# USB-Isolator_v10.net
KiCad netlist of a schematic drawn in EAGLE
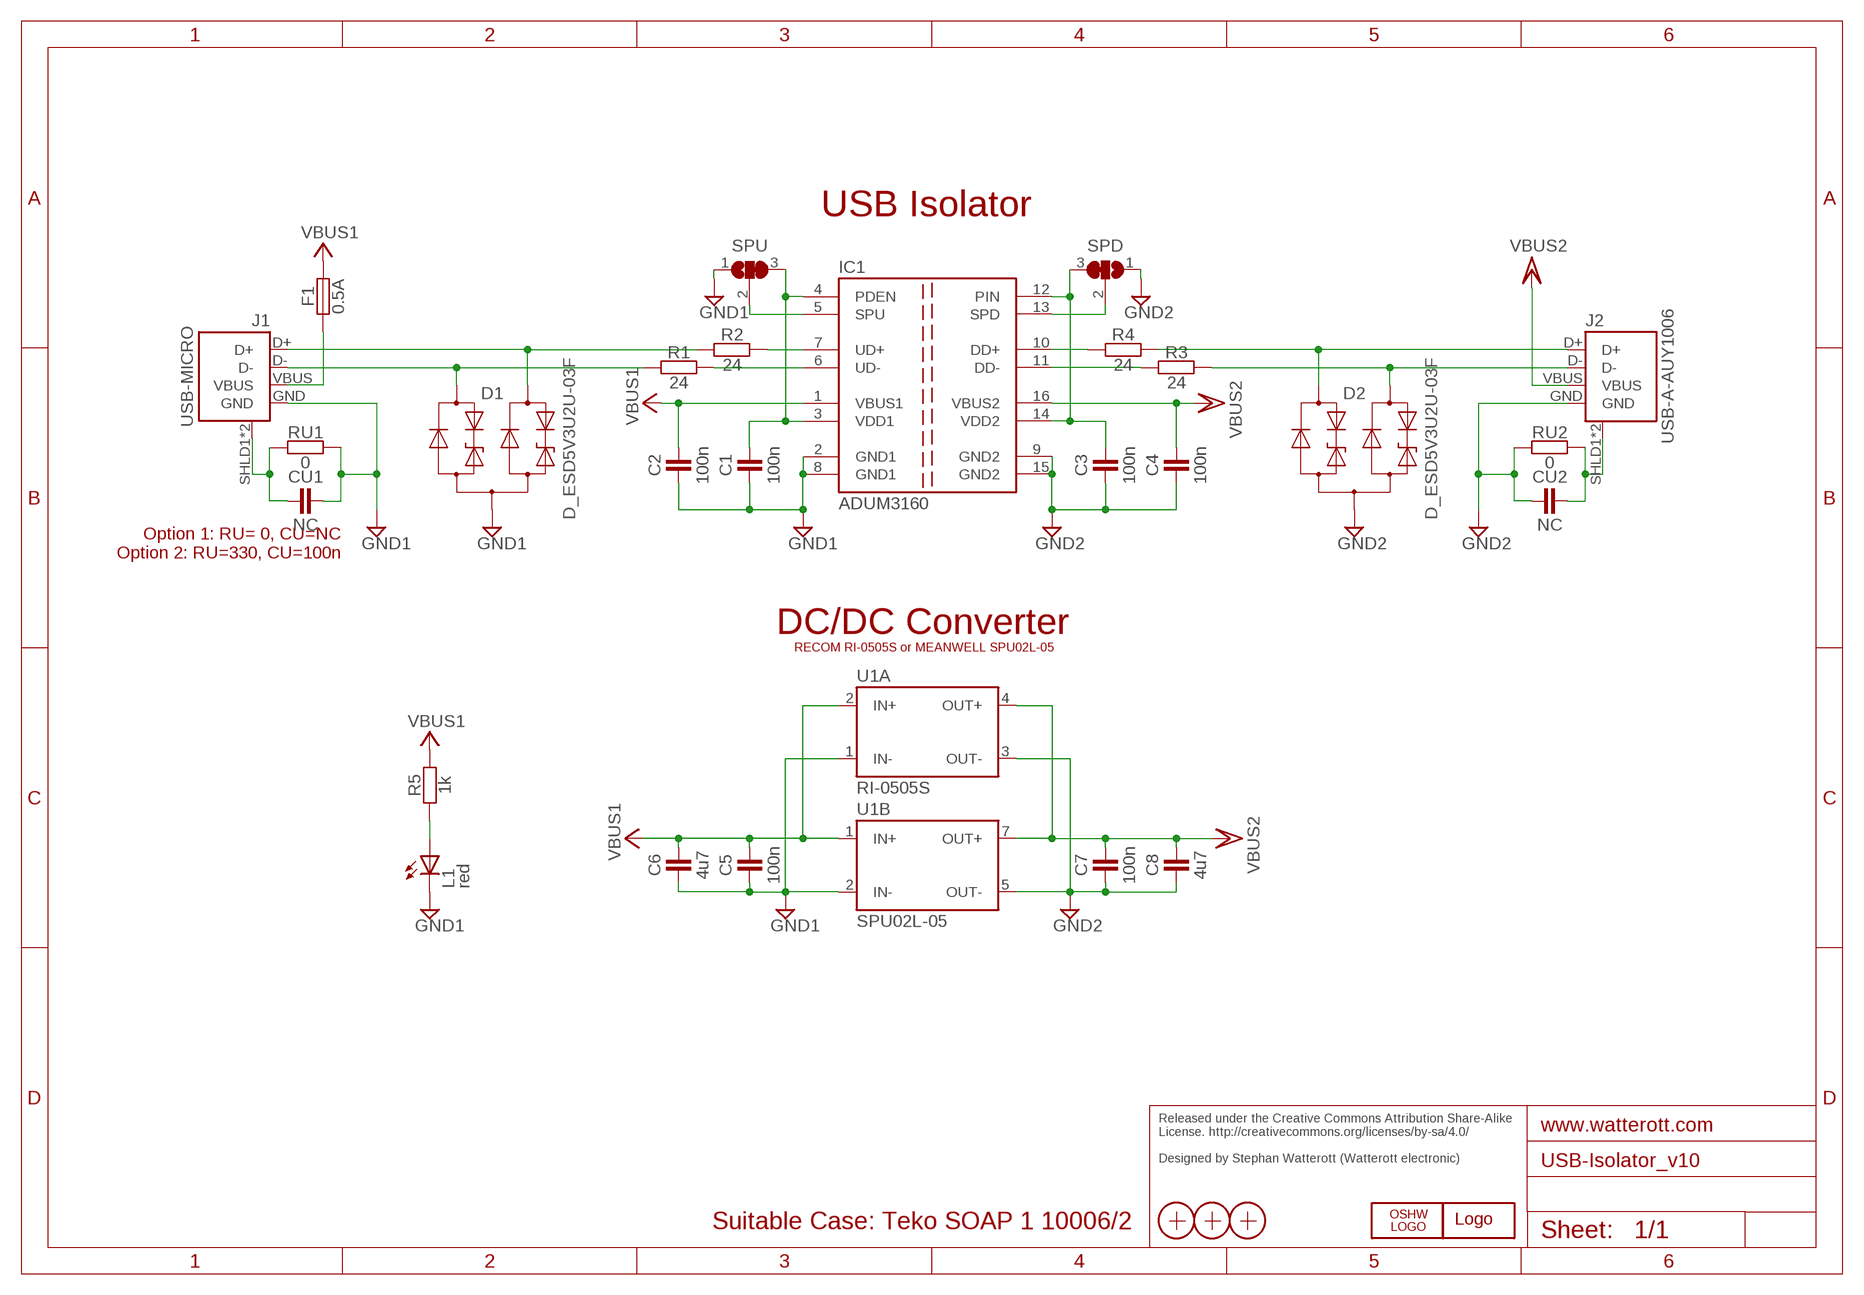
[diagram p0: schematic, sheet 1]

(export (version "E")
  (design (tool "Eeschema 10.0.6"))
  (components
    (comp (ref "C1")
      (value "100n")
      (footprint "eagle-import:R0603")
      (libsource (lib "eagle-import") (part "CAPACITOR-C0603"))
    )
    (comp (ref "C2")
      (value "100n")
      (footprint "eagle-import:R0603")
      (libsource (lib "eagle-import") (part "CAPACITOR-C0603"))
    )
    (comp (ref "C3")
      (value "100n")
      (footprint "eagle-import:R0603")
      (libsource (lib "eagle-import") (part "CAPACITOR-C0603"))
    )
    (comp (ref "C4")
      (value "100n")
      (footprint "eagle-import:R0603")
      (libsource (lib "eagle-import") (part "CAPACITOR-C0603"))
    )
    (comp (ref "C5")
      (value "100n")
      (footprint "eagle-import:R0603")
      (libsource (lib "eagle-import") (part "CAPACITOR-C0603"))
    )
    (comp (ref "C6")
      (value "4u7")
      (footprint "eagle-import:R1206")
      (libsource (lib "eagle-import") (part "CAPACITOR-C1206"))
    )
    (comp (ref "C7")
      (value "100n")
      (footprint "eagle-import:R0603")
      (libsource (lib "eagle-import") (part "CAPACITOR-C0603"))
    )
    (comp (ref "C8")
      (value "4u7")
      (footprint "eagle-import:R1206")
      (libsource (lib "eagle-import") (part "CAPACITOR-C1206"))
    )
    (comp (ref "CU1")
      (value "NC")
      (footprint "eagle-import:R0603")
      (libsource (lib "eagle-import") (part "CAPACITOR-C0603"))
    )
    (comp (ref "CU2")
      (value "NC")
      (footprint "eagle-import:R0603")
      (libsource (lib "eagle-import") (part "CAPACITOR-C0603"))
    )
    (comp (ref "D1")
      (value "D_ESD5V3U2U-03F")
      (footprint "eagle-import:TSFP3")
      (libsource (lib "eagle-import") (part "D_ESD5V3U2U-03F"))
    )
    (comp (ref "D2")
      (value "D_ESD5V3U2U-03F")
      (footprint "eagle-import:TSFP3")
      (libsource (lib "eagle-import") (part "D_ESD5V3U2U-03F"))
    )
    (comp (ref "F1")
      (value "0.5A")
      (footprint "eagle-import:R0805")
      (libsource (lib "eagle-import") (part "FUSE-0805"))
    )
    (comp (ref "IC1")
      (value "ADUM3160")
      (footprint "eagle-import:SO16W")
      (libsource (lib "eagle-import") (part "ADUM3160"))
    )
    (comp (ref "J1")
      (value "USB-MICRO")
      (footprint "eagle-import:USB-MICRO-10103594")
      (libsource (lib "eagle-import") (part "USB-MICRO"))
    )
    (comp (ref "J2")
      (value "USB-A-AUY1006")
      (footprint "eagle-import:USB-AU-Y1006-R")
      (fields (field (name "MANUFACTURER") "AU-Y1006-R"))
      (libsource (lib "eagle-import") (part "USB-A-AUY1006"))
    )
    (comp (ref "L1")
      (value "red")
      (footprint "eagle-import:LED_0603")
      (libsource (lib "eagle-import") (part "LED-0603"))
    )
    (comp (ref "LOGO2")
      (value "OSHW_LOGOX0070")
      (footprint "eagle-import:OSHW_6X70")
      (libsource (lib "eagle-import") (part "OSHW_LOGOX0070"))
    )
    (comp (ref "LOGO3")
      (value "LOGO-S_PLACE_M")
      (footprint "eagle-import:SPARK_TPLACE_M")
      (libsource (lib "eagle-import") (part "LOGO-S_PLACE_M"))
    )
    (comp (ref "R1")
      (value "24")
      (footprint "eagle-import:R0603")
      (libsource (lib "eagle-import") (part "RESISTOR-R0603"))
    )
    (comp (ref "R2")
      (value "24")
      (footprint "eagle-import:R0603")
      (libsource (lib "eagle-import") (part "RESISTOR-R0603"))
    )
    (comp (ref "R3")
      (value "24")
      (footprint "eagle-import:R0603")
      (libsource (lib "eagle-import") (part "RESISTOR-R0603"))
    )
    (comp (ref "R4")
      (value "24")
      (footprint "eagle-import:R0603")
      (libsource (lib "eagle-import") (part "RESISTOR-R0603"))
    )
    (comp (ref "R5")
      (value "1k")
      (footprint "eagle-import:R0603")
      (libsource (lib "eagle-import") (part "RESISTOR-R0603"))
    )
    (comp (ref "RU1")
      (value "0")
      (footprint "eagle-import:R0603")
      (libsource (lib "eagle-import") (part "RESISTOR-R0603"))
    )
    (comp (ref "RU2")
      (value "0")
      (footprint "eagle-import:R0603")
      (libsource (lib "eagle-import") (part "RESISTOR-R0603"))
    )
    (comp (ref "SPD")
      (value "JUMPER3")
      (footprint "eagle-import:JUMPER3")
      (libsource (lib "eagle-import") (part "JUMPER3"))
    )
    (comp (ref "SPU")
      (value "JUMPER3")
      (footprint "eagle-import:JUMPER3")
      (libsource (lib "eagle-import") (part "JUMPER3"))
    )
    (comp (ref "U1A")
      (value "RI-0505S")
      (footprint "eagle-import:RECOM_SIP4_RI")
      (libsource (lib "eagle-import") (part "DC/DC-RI"))
    )
    (comp (ref "U1B")
      (value "SPU02L-05")
      (footprint "eagle-import:MEANWELL_SIP7_SPU02")
      (libsource (lib "eagle-import") (part "DC/DC-SPU02"))
    )
    (comp (ref "X1")
      (value "PASSER-07")
      (footprint "eagle-import:PASSER_07MM")
      (libsource (lib "eagle-import") (part "PASSER-07"))
    )
    (comp (ref "X2")
      (value "PASSER-07")
      (footprint "eagle-import:PASSER_07MM")
      (libsource (lib "eagle-import") (part "PASSER-07"))
    )
    (comp (ref "X3")
      (value "PASSER-07")
      (footprint "eagle-import:PASSER_07MM")
      (libsource (lib "eagle-import") (part "PASSER-07"))
    )
  )
  (nets
    (net (code "1") (name "GND1") (class "Default")
      (node (ref "C1") (pin "1") (pinfunction "1_1") (pintype "passive"))
      (node (ref "C2") (pin "1") (pinfunction "1_1") (pintype "passive"))
      (node (ref "C5") (pin "1") (pinfunction "1_1") (pintype "passive"))
      (node (ref "C6") (pin "1") (pinfunction "1_1") (pintype "passive"))
      (node (ref "CU1") (pin "2") (pinfunction "2_2") (pintype "passive"))
      (node (ref "D1") (pin "3") (pinfunction "A_3") (pintype "passive"))
      (node (ref "IC1") (pin "2") (pinfunction "GND1_2") (pintype "power_in"))
      (node (ref "IC1") (pin "8") (pinfunction "GND1_8") (pintype "power_in"))
      (node (ref "J1") (pin "GND") (pinfunction "GND_GND") (pintype "power_in"))
      (node (ref "L1") (pin "C") (pinfunction "C_C") (pintype "passive"))
      (node (ref "RU1") (pin "2") (pinfunction "2_2") (pintype "passive"))
      (node (ref "SPU") (pin "1") (pinfunction "1_1") (pintype "passive"))
      (node (ref "U1A") (pin "1") (pinfunction "IN-_1") (pintype "power_in"))
      (node (ref "U1B") (pin "2") (pinfunction "IN-_2") (pintype "power_in"))
    )
    (net (code "2") (name "GND2") (class "Default")
      (node (ref "C3") (pin "1") (pinfunction "1_1") (pintype "passive"))
      (node (ref "C4") (pin "1") (pinfunction "1_1") (pintype "passive"))
      (node (ref "C7") (pin "1") (pinfunction "1_1") (pintype "passive"))
      (node (ref "C8") (pin "1") (pinfunction "1_1") (pintype "passive"))
      (node (ref "CU2") (pin "1") (pinfunction "1_1") (pintype "passive"))
      (node (ref "D2") (pin "3") (pinfunction "A_3") (pintype "passive"))
      (node (ref "IC1") (pin "15") (pinfunction "GND2_15") (pintype "power_in"))
      (node (ref "IC1") (pin "9") (pinfunction "GND2_9") (pintype "power_in"))
      (node (ref "J2") (pin "GND") (pinfunction "GND_GND") (pintype "power_in"))
      (node (ref "RU2") (pin "1") (pinfunction "1_1") (pintype "passive"))
      (node (ref "SPD") (pin "1") (pinfunction "1_1") (pintype "passive"))
      (node (ref "U1A") (pin "3") (pinfunction "OUT-_3") (pintype "power_in"))
      (node (ref "U1B") (pin "5") (pinfunction "OUT-_5") (pintype "power_in"))
    )
    (net (code "3") (name "Net-(CU1-Pad1)") (class "Default")
      (node (ref "CU1") (pin "1") (pinfunction "1_1") (pintype "passive"))
      (node (ref "J1") (pin "SHLD1") (pinfunction "SHIELD_SHLD1") (pintype "passive"))
      (node (ref "J1") (pin "SHLD2") (pinfunction "SHIELD_SHLD2") (pintype "passive"))
      (node (ref "RU1") (pin "1") (pinfunction "1_1") (pintype "passive"))
    )
    (net (code "4") (name "Net-(CU2-Pad2)") (class "Default")
      (node (ref "CU2") (pin "2") (pinfunction "2_2") (pintype "passive"))
      (node (ref "J2") (pin "SHLD1") (pinfunction "SHIELD_SHLD1") (pintype "passive"))
      (node (ref "J2") (pin "SHLD2") (pinfunction "SHIELD_SHLD2") (pintype "passive"))
      (node (ref "RU2") (pin "2") (pinfunction "2_2") (pintype "passive"))
    )
    (net (code "5") (name "Net-(D1-C1)") (class "Default")
      (node (ref "D1") (pin "1") (pinfunction "C1_1") (pintype "passive"))
      (node (ref "J1") (pin "D-") (pinfunction "D-_D-") (pintype "bidirectional"))
      (node (ref "R1") (pin "1") (pinfunction "1_1") (pintype "passive"))
    )
    (net (code "6") (name "Net-(D1-C2)") (class "Default")
      (node (ref "D1") (pin "2") (pinfunction "C2_2") (pintype "passive"))
      (node (ref "J1") (pin "D+") (pinfunction "D+_D+") (pintype "bidirectional"))
      (node (ref "R2") (pin "1") (pinfunction "1_1") (pintype "passive"))
    )
    (net (code "7") (name "Net-(D2-C1)") (class "Default")
      (node (ref "D2") (pin "1") (pinfunction "C1_1") (pintype "passive"))
      (node (ref "J2") (pin "D+") (pinfunction "D+_D+") (pintype "bidirectional"))
      (node (ref "R4") (pin "2") (pinfunction "2_2") (pintype "passive"))
    )
    (net (code "8") (name "Net-(D2-C2)") (class "Default")
      (node (ref "D2") (pin "2") (pinfunction "C2_2") (pintype "passive"))
      (node (ref "J2") (pin "D-") (pinfunction "D-_D-") (pintype "bidirectional"))
      (node (ref "R3") (pin "2") (pinfunction "2_2") (pintype "passive"))
    )
    (net (code "9") (name "Net-(F1-Pad1)") (class "Default")
      (node (ref "F1") (pin "1") (pinfunction "1_1") (pintype "passive"))
      (node (ref "J1") (pin "VBUS") (pinfunction "VBUS_VBUS") (pintype "power_in"))
    )
    (net (code "10") (name "Net-(IC1-DD+)") (class "Default")
      (node (ref "IC1") (pin "10") (pinfunction "DD+_10") (pintype "bidirectional"))
      (node (ref "R4") (pin "1") (pinfunction "1_1") (pintype "passive"))
    )
    (net (code "11") (name "Net-(IC1-DD-)") (class "Default")
      (node (ref "IC1") (pin "11") (pinfunction "DD-_11") (pintype "bidirectional"))
      (node (ref "R3") (pin "1") (pinfunction "1_1") (pintype "passive"))
    )
    (net (code "12") (name "Net-(IC1-PDEN)") (class "Default")
      (node (ref "C1") (pin "2") (pinfunction "2_2") (pintype "passive"))
      (node (ref "IC1") (pin "3") (pinfunction "VDD1_3") (pintype "power_in"))
      (node (ref "IC1") (pin "4") (pinfunction "PDEN_4") (pintype "input"))
      (node (ref "SPU") (pin "3") (pinfunction "3_3") (pintype "passive"))
    )
    (net (code "13") (name "Net-(IC1-PIN)") (class "Default")
      (node (ref "C3") (pin "2") (pinfunction "2_2") (pintype "passive"))
      (node (ref "IC1") (pin "12") (pinfunction "PIN_12") (pintype "input"))
      (node (ref "IC1") (pin "14") (pinfunction "VDD2_14") (pintype "power_in"))
      (node (ref "SPD") (pin "3") (pinfunction "3_3") (pintype "passive"))
    )
    (net (code "14") (name "Net-(IC1-SPD)") (class "Default")
      (node (ref "IC1") (pin "13") (pinfunction "SPD_13") (pintype "input"))
      (node (ref "SPD") (pin "2") (pinfunction "2_2") (pintype "passive"))
    )
    (net (code "15") (name "Net-(IC1-SPU)") (class "Default")
      (node (ref "IC1") (pin "5") (pinfunction "SPU_5") (pintype "input"))
      (node (ref "SPU") (pin "2") (pinfunction "2_2") (pintype "passive"))
    )
    (net (code "16") (name "Net-(IC1-UD+)") (class "Default")
      (node (ref "IC1") (pin "7") (pinfunction "UD+_7") (pintype "bidirectional"))
      (node (ref "R2") (pin "2") (pinfunction "2_2") (pintype "passive"))
    )
    (net (code "17") (name "Net-(IC1-UD-)") (class "Default")
      (node (ref "IC1") (pin "6") (pinfunction "UD-_6") (pintype "bidirectional"))
      (node (ref "R1") (pin "2") (pinfunction "2_2") (pintype "passive"))
    )
    (net (code "18") (name "Net-(L1-PadA)") (class "Default")
      (node (ref "L1") (pin "A") (pinfunction "A_A") (pintype "passive"))
      (node (ref "R5") (pin "1") (pinfunction "1_1") (pintype "passive"))
    )
    (net (code "19") (name "VBUS1") (class "Default")
      (node (ref "C2") (pin "2") (pinfunction "2_2") (pintype "passive"))
      (node (ref "C5") (pin "2") (pinfunction "2_2") (pintype "passive"))
      (node (ref "C6") (pin "2") (pinfunction "2_2") (pintype "passive"))
      (node (ref "F1") (pin "2") (pinfunction "2_2") (pintype "passive"))
      (node (ref "IC1") (pin "1") (pinfunction "VBUS1_1") (pintype "power_in"))
      (node (ref "R5") (pin "2") (pinfunction "2_2") (pintype "passive"))
      (node (ref "U1A") (pin "2") (pinfunction "IN+_2") (pintype "power_in"))
      (node (ref "U1B") (pin "1") (pinfunction "IN+_1") (pintype "power_in"))
    )
    (net (code "20") (name "VBUS2") (class "Default")
      (node (ref "C4") (pin "2") (pinfunction "2_2") (pintype "passive"))
      (node (ref "C7") (pin "2") (pinfunction "2_2") (pintype "passive"))
      (node (ref "C8") (pin "2") (pinfunction "2_2") (pintype "passive"))
      (node (ref "IC1") (pin "16") (pinfunction "VBUS2_16") (pintype "power_in"))
      (node (ref "J2") (pin "VBUS") (pinfunction "VBUS_VBUS") (pintype "power_in"))
      (node (ref "U1A") (pin "4") (pinfunction "OUT+_4") (pintype "power_in"))
      (node (ref "U1B") (pin "7") (pinfunction "OUT+_7") (pintype "power_in"))
    )
  )
)
